# mainBoard.net
KiCad netlist of a schematic drawn in EAGLE
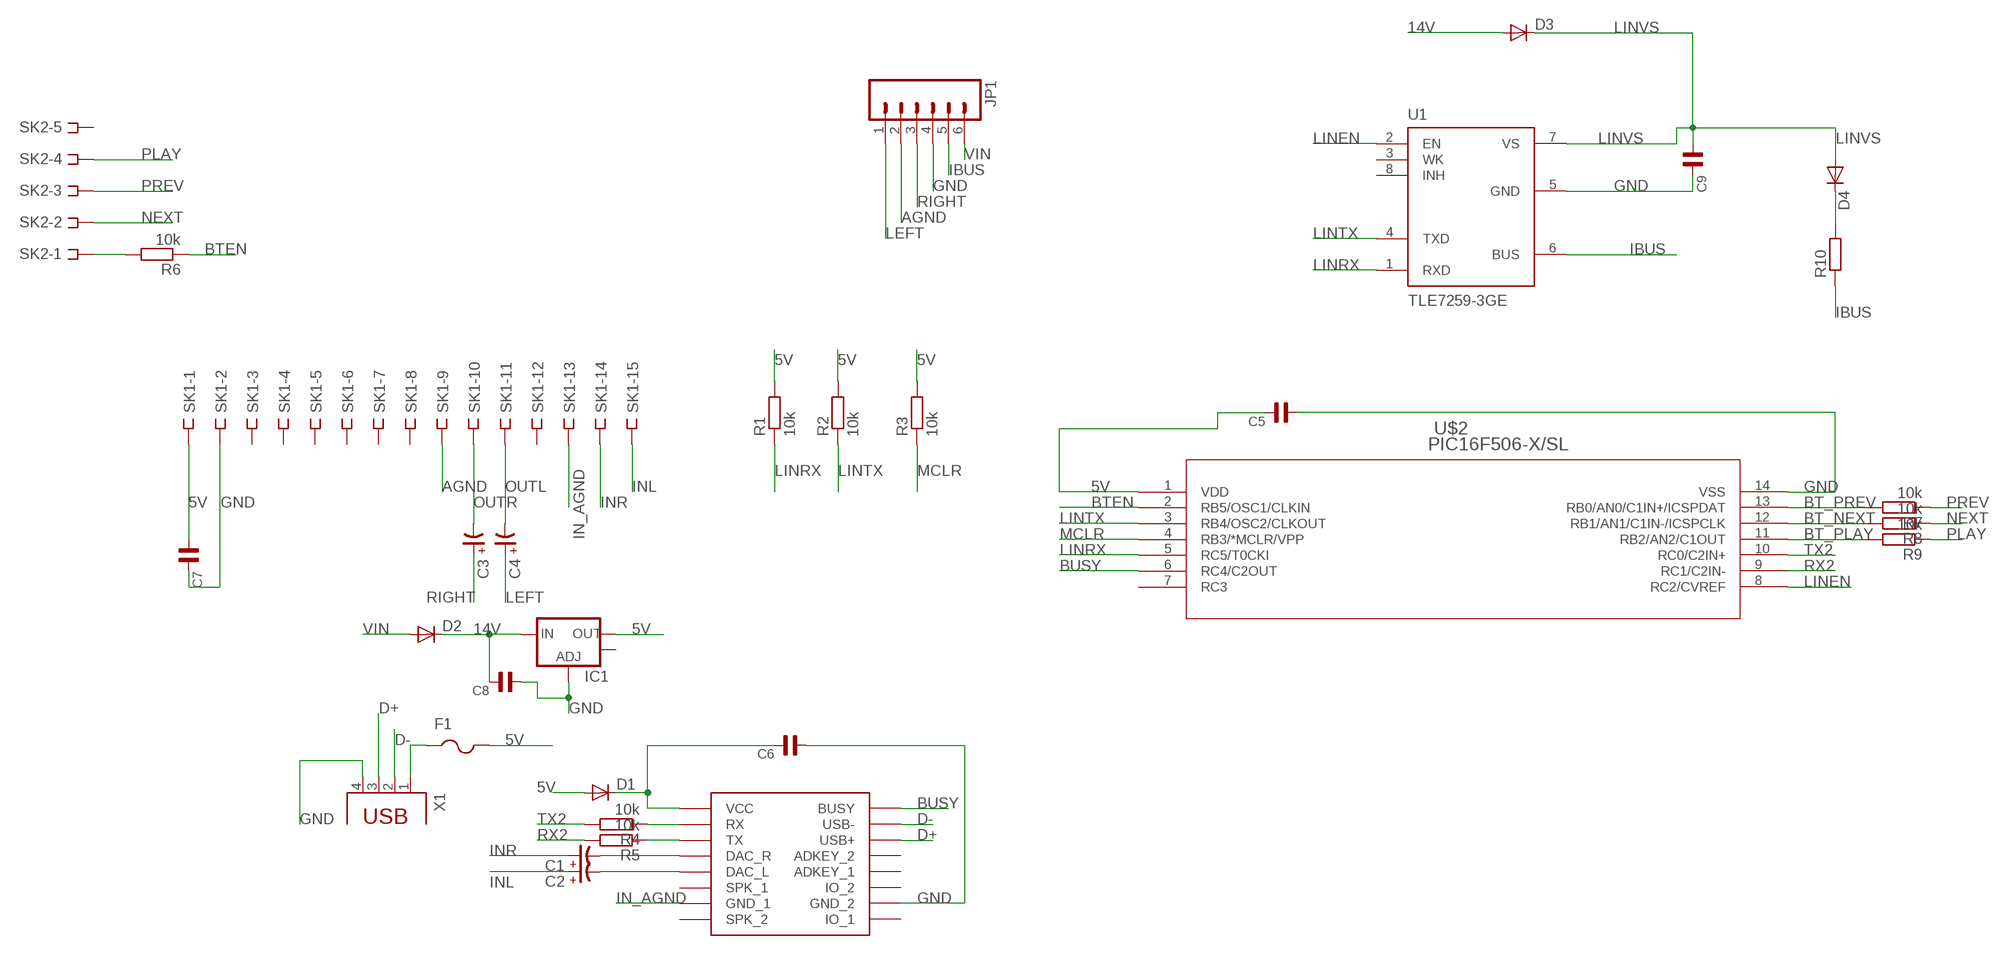
[diagram p0: schematic, sheet 1]

(export (version "E")
  (design (tool "Eeschema 10.0.6"))
  (components
    (comp (ref "C1")
      (value "CP-3258-TE-B")
      (footprint "eagle-import:3528-TE-B")
      (libsource (lib "eagle-import") (part "CP-3258-TE-B"))
    )
    (comp (ref "C2")
      (value "CP-3258-TE-B")
      (footprint "eagle-import:3528-TE-B")
      (libsource (lib "eagle-import") (part "CP-3258-TE-B"))
    )
    (comp (ref "C3")
      (value "CP-3258-TE-B")
      (footprint "eagle-import:3528-TE-B")
      (libsource (lib "eagle-import") (part "CP-3258-TE-B"))
    )
    (comp (ref "C4")
      (value "CP-3258-TE-B")
      (footprint "eagle-import:3528-TE-B")
      (libsource (lib "eagle-import") (part "CP-3258-TE-B"))
    )
    (comp (ref "C5")
      (value "C0603")
      (footprint "eagle-import:0603")
      (libsource (lib "eagle-import") (part "C0603"))
    )
    (comp (ref "C6")
      (value "C0603")
      (footprint "eagle-import:0603")
      (libsource (lib "eagle-import") (part "C0603"))
    )
    (comp (ref "C7")
      (value "C0603")
      (footprint "eagle-import:0603")
      (libsource (lib "eagle-import") (part "C0603"))
    )
    (comp (ref "C8")
      (value "C1206")
      (footprint "eagle-import:1206")
      (libsource (lib "eagle-import") (part "C1206"))
    )
    (comp (ref "C9")
      (value "C0603")
      (footprint "eagle-import:0603")
      (libsource (lib "eagle-import") (part "C0603"))
    )
    (comp (ref "D1")
      (value "DIODESMA-ALT")
      (footprint "eagle-import:SMA-DIODE_ALT")
      (libsource (lib "eagle-import") (part "DIODESMA-ALT"))
    )
    (comp (ref "D2")
      (value "DIODESMA-ALT")
      (footprint "eagle-import:SMA-DIODE_ALT")
      (libsource (lib "eagle-import") (part "DIODESMA-ALT"))
    )
    (comp (ref "D3")
      (value "DIODE-SOD80C")
      (footprint "eagle-import:SOD80C")
      (libsource (lib "eagle-import") (part "DIODE-SOD80C"))
    )
    (comp (ref "D4")
      (value "DIODE-SOD80C")
      (footprint "eagle-import:SOD80C")
      (libsource (lib "eagle-import") (part "DIODE-SOD80C"))
    )
    (comp (ref "F1")
      (value "PTCFUSE-1812")
      (footprint "eagle-import:1812")
      (libsource (lib "eagle-import") (part "PTCFUSE-1812"))
    )
    (comp (ref "IC1")
      (value "V_REG_LM1117SOT223")
      (footprint "eagle-import:SOT223")
      (libsource (lib "eagle-import") (part "V_REG_LM1117SOT223"))
    )
    (comp (ref "JP1")
      (value "M06LONGPADS")
      (footprint "eagle-import:1X06_LONGPADS")
      (libsource (lib "eagle-import") (part "M06LONGPADS"))
    )
    (comp (ref "R1")
      (value "10k")
      (footprint "eagle-import:R0603")
      (libsource (lib "eagle-import") (part "R-EU_R0603"))
    )
    (comp (ref "R2")
      (value "10k")
      (footprint "eagle-import:R0603")
      (libsource (lib "eagle-import") (part "R-EU_R0603"))
    )
    (comp (ref "R3")
      (value "10k")
      (footprint "eagle-import:R0603")
      (libsource (lib "eagle-import") (part "R-EU_R0603"))
    )
    (comp (ref "R4")
      (value "10k")
      (footprint "eagle-import:R0603")
      (libsource (lib "eagle-import") (part "R-EU_R0603"))
    )
    (comp (ref "R5")
      (value "10k")
      (footprint "eagle-import:R0603")
      (libsource (lib "eagle-import") (part "R-EU_R0603"))
    )
    (comp (ref "R6")
      (value "10k")
      (footprint "eagle-import:R0603")
      (libsource (lib "eagle-import") (part "R-EU_R0603"))
    )
    (comp (ref "R7")
      (value "10k")
      (footprint "eagle-import:R0603")
      (libsource (lib "eagle-import") (part "R-EU_R0603"))
    )
    (comp (ref "R8")
      (value "10k")
      (footprint "eagle-import:R0603")
      (libsource (lib "eagle-import") (part "R-EU_R0603"))
    )
    (comp (ref "R9")
      (value "10k")
      (footprint "eagle-import:R0603")
      (libsource (lib "eagle-import") (part "R-EU_R0603"))
    )
    (comp (ref "R10")
      (value "R-EU_R0603")
      (footprint "eagle-import:R0603")
      (libsource (lib "eagle-import") (part "R-EU_R0603"))
    )
    (comp (ref "SK1")
      (value "DF3-15S")
      (footprint "eagle-import:DF3S-15")
      (libsource (lib "eagle-import") (part "DF3-15S"))
    )
    (comp (ref "SK2")
      (value "DF3-05S")
      (footprint "eagle-import:DF3S-05")
      (libsource (lib "eagle-import") (part "DF3-05S"))
    )
    (comp (ref "U$1")
      (value "DFPLAYER")
      (footprint "eagle-import:DFPLAYER")
      (libsource (lib "eagle-import") (part "DFPLAYER"))
    )
    (comp (ref "U$2")
      (value "PIC16F506-X/SL")
      (footprint "eagle-import:SOIC14-N_MC")
      (libsource (lib "eagle-import") (part "PIC16F506-X/SL"))
    )
    (comp (ref "U1")
      (value "TLE7259-3GE")
      (footprint "eagle-import:SOIC127P600X175-8N-3")
      (libsource (lib "eagle-import") (part "TLE7259-3GE"))
    )
    (comp (ref "X1")
      (value "PN87520")
      (footprint "eagle-import:PN87520")
      (libsource (lib "eagle-import") (part "PN87520"))
    )
  )
  (nets
    (net (code "1") (name "/5V") (class "Default")
      (node (ref "C5") (pin "2") (pinfunction "2_2") (pintype "passive"))
      (node (ref "C7") (pin "1") (pinfunction "1_1") (pintype "passive"))
      (node (ref "D1") (pin "A") (pinfunction "A_A") (pintype "passive"))
      (node (ref "F1") (pin "2") (pinfunction "2_2") (pintype "passive"))
      (node (ref "IC1") (pin "2") (pinfunction "OUT_2") (pintype "output"))
      (node (ref "R1") (pin "2") (pinfunction "2_2") (pintype "passive"))
      (node (ref "R2") (pin "2") (pinfunction "2_2") (pintype "passive"))
      (node (ref "R3") (pin "2") (pinfunction "2_2") (pintype "passive"))
      (node (ref "SK1") (pin "1") (pinfunction "S_1") (pintype "passive"))
      (node (ref "U$2") (pin "1") (pinfunction "VDD_1") (pintype "passive"))
    )
    (net (code "2") (name "/14V") (class "Default")
      (node (ref "C8") (pin "2") (pinfunction "2_2") (pintype "passive"))
      (node (ref "D2") (pin "C") (pinfunction "C_C") (pintype "passive"))
      (node (ref "D3") (pin "A") (pinfunction "A_A") (pintype "passive"))
      (node (ref "IC1") (pin "3") (pinfunction "IN_3") (pintype "input"))
    )
    (net (code "3") (name "/AGND") (class "Default")
      (node (ref "JP1") (pin "2") (pinfunction "2_2") (pintype "passive"))
      (node (ref "SK1") (pin "9") (pinfunction "S_9") (pintype "passive"))
    )
    (net (code "4") (name "/BTEN") (class "Default")
      (node (ref "R6") (pin "1") (pinfunction "1_1") (pintype "passive"))
      (node (ref "U$2") (pin "2") (pinfunction "RB5/OSC1/CLKIN_2") (pintype "passive"))
    )
    (net (code "5") (name "/BT_NEXT") (class "Default")
      (node (ref "R8") (pin "2") (pinfunction "2_2") (pintype "passive"))
      (node (ref "U$2") (pin "12") (pinfunction "RB1/AN1/C1IN-/ICSPCLK_12") (pintype "passive"))
    )
    (net (code "6") (name "/BT_PLAY") (class "Default")
      (node (ref "R9") (pin "2") (pinfunction "2_2") (pintype "passive"))
      (node (ref "U$2") (pin "11") (pinfunction "RB2/AN2/C1OUT_11") (pintype "passive"))
    )
    (net (code "7") (name "/BT_PREV") (class "Default")
      (node (ref "R7") (pin "2") (pinfunction "2_2") (pintype "passive"))
      (node (ref "U$2") (pin "13") (pinfunction "RB0/AN0/C1IN+/ICSPDAT_13") (pintype "passive"))
    )
    (net (code "8") (name "/BUSY") (class "Default")
      (node (ref "U$1") (pin "BUSY") (pinfunction "BUSY_BUSY") (pintype "bidirectional"))
      (node (ref "U$2") (pin "6") (pinfunction "RC4/C2OUT_6") (pintype "passive"))
    )
    (net (code "9") (name "/D+") (class "Default")
      (node (ref "U$1") (pin "USB+") (pinfunction "USB+_USB+") (pintype "bidirectional"))
      (node (ref "X1") (pin "3") (pinfunction "3_3") (pintype "passive"))
    )
    (net (code "10") (name "/D-") (class "Default")
      (node (ref "U$1") (pin "USB-") (pinfunction "USB-_USB-") (pintype "bidirectional"))
      (node (ref "X1") (pin "2") (pinfunction "2_2") (pintype "passive"))
    )
    (net (code "11") (name "/GND") (class "Default")
      (node (ref "C5") (pin "1") (pinfunction "1_1") (pintype "passive"))
      (node (ref "C6") (pin "1") (pinfunction "1_1") (pintype "passive"))
      (node (ref "C7") (pin "2") (pinfunction "2_2") (pintype "passive"))
      (node (ref "C8") (pin "1") (pinfunction "1_1") (pintype "passive"))
      (node (ref "C9") (pin "2") (pinfunction "2_2") (pintype "passive"))
      (node (ref "IC1") (pin "1") (pinfunction "ADJ_1") (pintype "input"))
      (node (ref "JP1") (pin "4") (pinfunction "4_4") (pintype "passive"))
      (node (ref "SK1") (pin "2") (pinfunction "S_2") (pintype "passive"))
      (node (ref "U$1") (pin "GND_2") (pinfunction "GND_2_GND_2") (pintype "bidirectional"))
      (node (ref "U$2") (pin "14") (pinfunction "VSS_14") (pintype "passive"))
      (node (ref "U1") (pin "5") (pinfunction "GND_5") (pintype "power_in"))
      (node (ref "X1") (pin "4") (pinfunction "4_4") (pintype "passive"))
    )
    (net (code "12") (name "/IBUS") (class "Default")
      (node (ref "JP1") (pin "5") (pinfunction "5_5") (pintype "passive"))
      (node (ref "R10") (pin "1") (pinfunction "1_1") (pintype "passive"))
      (node (ref "U1") (pin "6") (pinfunction "BUS_6") (pintype "bidirectional"))
    )
    (net (code "13") (name "/INL") (class "Default")
      (node (ref "C2") (pin "+") (pinfunction "+_+") (pintype "passive"))
      (node (ref "SK1") (pin "15") (pinfunction "S_15") (pintype "passive"))
    )
    (net (code "14") (name "/INR") (class "Default")
      (node (ref "C1") (pin "+") (pinfunction "+_+") (pintype "passive"))
      (node (ref "SK1") (pin "14") (pinfunction "S_14") (pintype "passive"))
    )
    (net (code "15") (name "/IN_AGND") (class "Default")
      (node (ref "SK1") (pin "13") (pinfunction "S_13") (pintype "passive"))
      (node (ref "U$1") (pin "GND_1") (pinfunction "GND_1_GND_1") (pintype "bidirectional"))
    )
    (net (code "16") (name "/LEFT") (class "Default")
      (node (ref "C4") (pin "+") (pinfunction "+_+") (pintype "passive"))
      (node (ref "JP1") (pin "1") (pinfunction "1_1") (pintype "passive"))
    )
    (net (code "17") (name "/LINEN") (class "Default")
      (node (ref "U$2") (pin "8") (pinfunction "RC2/CVREF_8") (pintype "passive"))
      (node (ref "U1") (pin "2") (pinfunction "EN_2") (pintype "input"))
    )
    (net (code "18") (name "/LINRX") (class "Default")
      (node (ref "R1") (pin "1") (pinfunction "1_1") (pintype "passive"))
      (node (ref "U$2") (pin "5") (pinfunction "RC5/T0CKI_5") (pintype "passive"))
      (node (ref "U1") (pin "1") (pinfunction "RXD_1") (pintype "output"))
    )
    (net (code "19") (name "/LINTX") (class "Default")
      (node (ref "R2") (pin "1") (pinfunction "1_1") (pintype "passive"))
      (node (ref "U$2") (pin "3") (pinfunction "RB4/OSC2/CLKOUT_3") (pintype "passive"))
      (node (ref "U1") (pin "4") (pinfunction "TXD_4") (pintype "input"))
    )
    (net (code "20") (name "/LINVS") (class "Default")
      (node (ref "C9") (pin "1") (pinfunction "1_1") (pintype "passive"))
      (node (ref "D3") (pin "C") (pinfunction "C_C") (pintype "passive"))
      (node (ref "D4") (pin "A") (pinfunction "A_A") (pintype "passive"))
      (node (ref "U1") (pin "7") (pinfunction "VS_7") (pintype "power_in"))
    )
    (net (code "21") (name "/MCLR") (class "Default")
      (node (ref "R3") (pin "1") (pinfunction "1_1") (pintype "passive"))
      (node (ref "U$2") (pin "4") (pinfunction "RB3/*MCLR/VPP_4") (pintype "passive"))
    )
    (net (code "22") (name "/NEXT") (class "Default")
      (node (ref "R8") (pin "1") (pinfunction "1_1") (pintype "passive"))
      (node (ref "SK2") (pin "2") (pinfunction "S_2") (pintype "passive"))
    )
    (net (code "23") (name "/OUTL") (class "Default")
      (node (ref "C4") (pin "-") (pinfunction "-_-") (pintype "passive"))
      (node (ref "SK1") (pin "11") (pinfunction "S_11") (pintype "passive"))
    )
    (net (code "24") (name "/OUTR") (class "Default")
      (node (ref "C3") (pin "-") (pinfunction "-_-") (pintype "passive"))
      (node (ref "SK1") (pin "10") (pinfunction "S_10") (pintype "passive"))
    )
    (net (code "25") (name "/PLAY") (class "Default")
      (node (ref "R9") (pin "1") (pinfunction "1_1") (pintype "passive"))
      (node (ref "SK2") (pin "4") (pinfunction "S_4") (pintype "passive"))
    )
    (net (code "26") (name "/PREV") (class "Default")
      (node (ref "R7") (pin "1") (pinfunction "1_1") (pintype "passive"))
      (node (ref "SK2") (pin "3") (pinfunction "S_3") (pintype "passive"))
    )
    (net (code "27") (name "/RIGHT") (class "Default")
      (node (ref "C3") (pin "+") (pinfunction "+_+") (pintype "passive"))
      (node (ref "JP1") (pin "3") (pinfunction "3_3") (pintype "passive"))
    )
    (net (code "28") (name "/RX2") (class "Default")
      (node (ref "R5") (pin "2") (pinfunction "2_2") (pintype "passive"))
      (node (ref "U$2") (pin "9") (pinfunction "RC1/C2IN-_9") (pintype "passive"))
    )
    (net (code "29") (name "/TX2") (class "Default")
      (node (ref "R4") (pin "2") (pinfunction "2_2") (pintype "passive"))
      (node (ref "U$2") (pin "10") (pinfunction "RC0/C2IN+_10") (pintype "passive"))
    )
    (net (code "30") (name "/VIN") (class "Default")
      (node (ref "D2") (pin "A") (pinfunction "A_A") (pintype "passive"))
      (node (ref "JP1") (pin "6") (pinfunction "6_6") (pintype "passive"))
    )
    (net (code "31") (name "Net-(C1-Pad-)") (class "Default")
      (node (ref "C1") (pin "-") (pinfunction "-_-") (pintype "passive"))
      (node (ref "U$1") (pin "DAC_R") (pinfunction "DAC_R_DAC_R") (pintype "bidirectional"))
    )
    (net (code "32") (name "Net-(C2-Pad-)") (class "Default")
      (node (ref "C2") (pin "-") (pinfunction "-_-") (pintype "passive"))
      (node (ref "U$1") (pin "DAC_L") (pinfunction "DAC_L_DAC_L") (pintype "bidirectional"))
    )
    (net (code "33") (name "Net-(C6-Pad2)") (class "Default")
      (node (ref "C6") (pin "2") (pinfunction "2_2") (pintype "passive"))
      (node (ref "D1") (pin "C") (pinfunction "C_C") (pintype "passive"))
      (node (ref "U$1") (pin "VCC") (pinfunction "VCC_VCC") (pintype "bidirectional"))
    )
    (net (code "34") (name "Net-(D4-PadC)") (class "Default")
      (node (ref "D4") (pin "C") (pinfunction "C_C") (pintype "passive"))
      (node (ref "R10") (pin "2") (pinfunction "2_2") (pintype "passive"))
    )
    (net (code "35") (name "Net-(F1-Pad1)") (class "Default")
      (node (ref "F1") (pin "1") (pinfunction "1_1") (pintype "passive"))
      (node (ref "X1") (pin "1") (pinfunction "1_1") (pintype "passive"))
    )
    (net (code "36") (name "Net-(R4-Pad1)") (class "Default")
      (node (ref "R4") (pin "1") (pinfunction "1_1") (pintype "passive"))
      (node (ref "U$1") (pin "RX") (pinfunction "RX_RX") (pintype "bidirectional"))
    )
    (net (code "37") (name "Net-(R5-Pad1)") (class "Default")
      (node (ref "R5") (pin "1") (pinfunction "1_1") (pintype "passive"))
      (node (ref "U$1") (pin "TX") (pinfunction "TX_TX") (pintype "bidirectional"))
    )
    (net (code "38") (name "Net-(SK2A-S)") (class "Default")
      (node (ref "R6") (pin "2") (pinfunction "2_2") (pintype "passive"))
      (node (ref "SK2") (pin "1") (pinfunction "S_1") (pintype "passive"))
    )
    (net (code "39") (name "unconnected-(IC1-OUT-Pad4)") (class "Default")
      (node (ref "IC1") (pin "4") (pinfunction "OUT_4") (pintype "output"))
    )
    (net (code "40") (name "unconnected-(SK1D-S-Pad12)") (class "Default")
      (node (ref "SK1") (pin "12") (pinfunction "S_12") (pintype "passive"))
    )
    (net (code "41") (name "unconnected-(SK1I-S-Pad3)") (class "Default")
      (node (ref "SK1") (pin "3") (pinfunction "S_3") (pintype "passive"))
    )
    (net (code "42") (name "unconnected-(SK1J-S-Pad4)") (class "Default")
      (node (ref "SK1") (pin "4") (pinfunction "S_4") (pintype "passive"))
    )
    (net (code "43") (name "unconnected-(SK1K-S-Pad5)") (class "Default")
      (node (ref "SK1") (pin "5") (pinfunction "S_5") (pintype "passive"))
    )
    (net (code "44") (name "unconnected-(SK1L-S-Pad6)") (class "Default")
      (node (ref "SK1") (pin "6") (pinfunction "S_6") (pintype "passive"))
    )
    (net (code "45") (name "unconnected-(SK1M-S-Pad7)") (class "Default")
      (node (ref "SK1") (pin "7") (pinfunction "S_7") (pintype "passive"))
    )
    (net (code "46") (name "unconnected-(SK1N-S-Pad8)") (class "Default")
      (node (ref "SK1") (pin "8") (pinfunction "S_8") (pintype "passive"))
    )
    (net (code "47") (name "unconnected-(SK2E-S-Pad5)") (class "Default")
      (node (ref "SK2") (pin "5") (pinfunction "S_5") (pintype "passive"))
    )
    (net (code "48") (name "unconnected-(U$1-ADKEY_1-PadADKEY1)") (class "Default")
      (node (ref "U$1") (pin "ADKEY1") (pinfunction "ADKEY_1_ADKEY1") (pintype "bidirectional"))
    )
    (net (code "49") (name "unconnected-(U$1-ADKEY_2-PadADKEY2)") (class "Default")
      (node (ref "U$1") (pin "ADKEY2") (pinfunction "ADKEY_2_ADKEY2") (pintype "bidirectional"))
    )
    (net (code "50") (name "unconnected-(U$1-IO_1-PadIO1)") (class "Default")
      (node (ref "U$1") (pin "IO1") (pinfunction "IO_1_IO1") (pintype "bidirectional"))
    )
    (net (code "51") (name "unconnected-(U$1-IO_2-PadIO2)") (class "Default")
      (node (ref "U$1") (pin "IO2") (pinfunction "IO_2_IO2") (pintype "bidirectional"))
    )
    (net (code "52") (name "unconnected-(U$1-SPK_1-PadSPK1)") (class "Default")
      (node (ref "U$1") (pin "SPK1") (pinfunction "SPK_1_SPK1") (pintype "bidirectional"))
    )
    (net (code "53") (name "unconnected-(U$1-SPK_2-PadSPK2)") (class "Default")
      (node (ref "U$1") (pin "SPK2") (pinfunction "SPK_2_SPK2") (pintype "bidirectional"))
    )
    (net (code "54") (name "unconnected-(U$2-RC3-Pad7)") (class "Default")
      (node (ref "U$2") (pin "7") (pinfunction "RC3_7") (pintype "passive"))
    )
    (net (code "55") (name "unconnected-(U1-INH-Pad8)") (class "Default")
      (node (ref "U1") (pin "8") (pinfunction "INH_8") (pintype "output"))
    )
    (net (code "56") (name "unconnected-(U1-WK-Pad3)") (class "Default")
      (node (ref "U1") (pin "3") (pinfunction "WK_3") (pintype "input"))
    )
  )
)
